# SCB_PLLs.net
KiCad netlist of a schematic drawn in Altium Designer
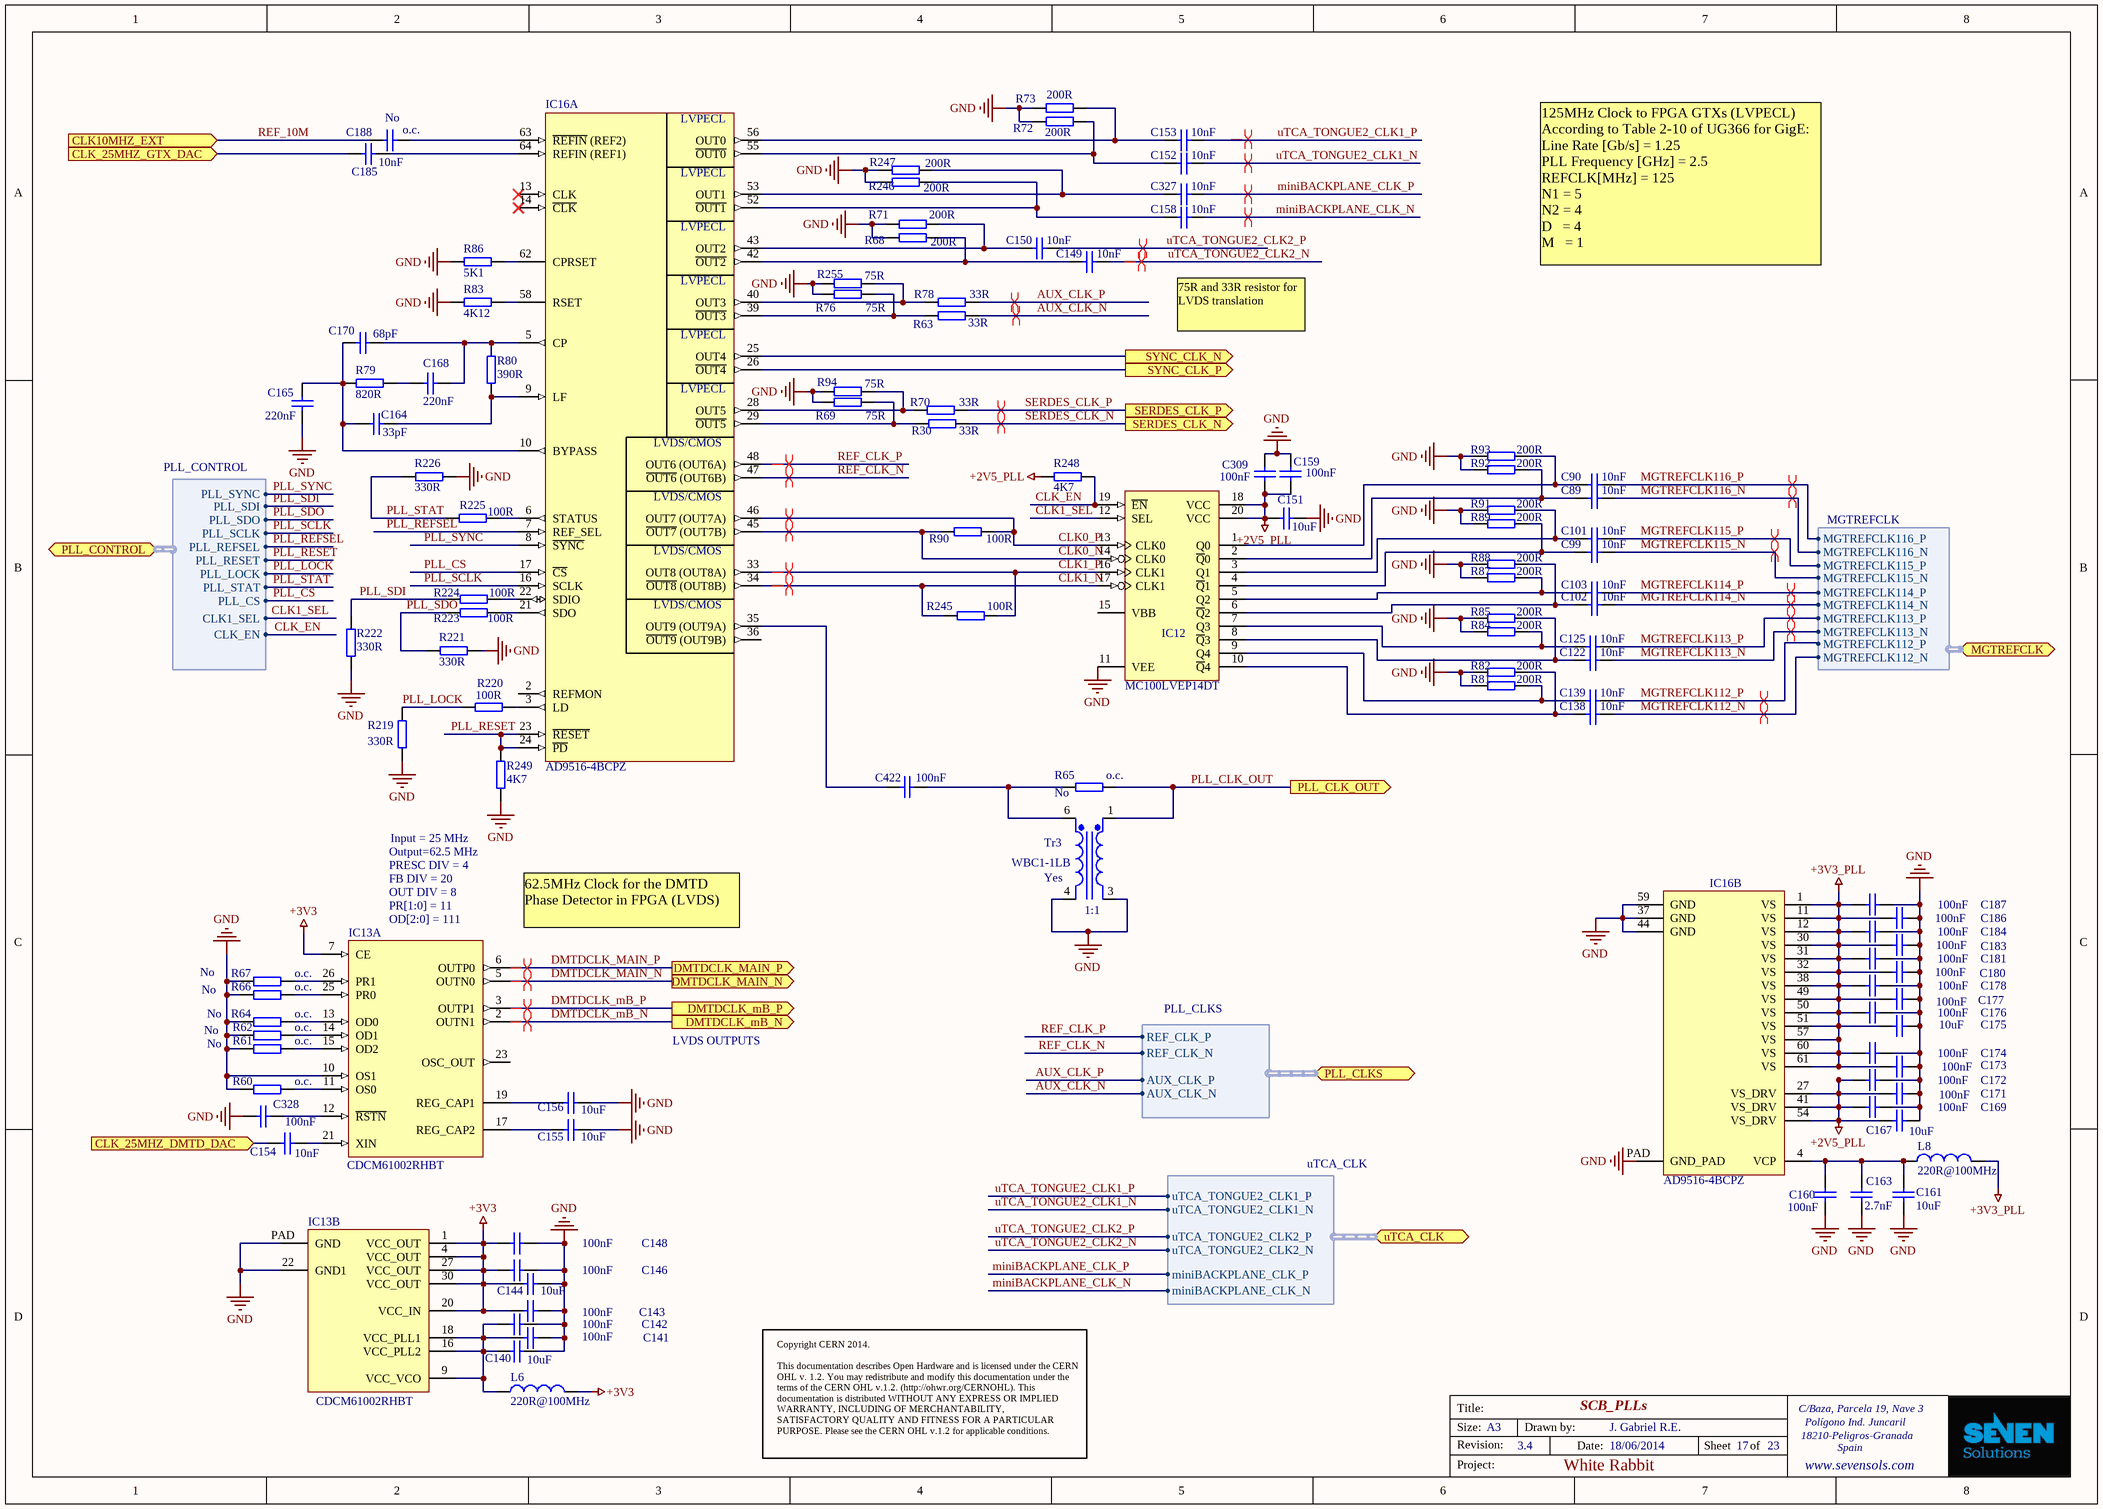
[diagram p0: SCB_PLLs.SchDoc]

(export (version "E")
  (design (tool "Eeschema 10.0.6"))
  (components
    (comp (ref "C89")
      (value "10nF")
      (footprint "CC1005-0402")
      (description "Capacitor")
      (fields (field (name "TOLERANCE") "±10%") (field (name "VOLTAGE") "25V"))
      (libsource (lib "wr_switch") (part "Cap"))
    )
    (comp (ref "C90")
      (value "10nF")
      (footprint "CC1005-0402")
      (description "Capacitor")
      (fields (field (name "TOLERANCE") "±10%") (field (name "VOLTAGE") "25V"))
      (libsource (lib "wr_switch") (part "Cap"))
    )
    (comp (ref "C99")
      (value "10nF")
      (footprint "CC1005-0402")
      (description "Capacitor")
      (fields (field (name "TOLERANCE") "±10%") (field (name "VOLTAGE") "25V"))
      (libsource (lib "wr_switch") (part "Cap"))
    )
    (comp (ref "C101")
      (value "10nF")
      (footprint "CC1005-0402")
      (description "Capacitor")
      (fields (field (name "TOLERANCE") "±10%") (field (name "VOLTAGE") "25V"))
      (libsource (lib "wr_switch") (part "Cap"))
    )
    (comp (ref "C102")
      (value "10nF")
      (footprint "CC1005-0402")
      (description "Capacitor")
      (fields (field (name "TOLERANCE") "±10%") (field (name "VOLTAGE") "25V"))
      (libsource (lib "wr_switch") (part "Cap"))
    )
    (comp (ref "C103")
      (value "10nF")
      (footprint "CC1005-0402")
      (description "Capacitor")
      (fields (field (name "TOLERANCE") "±10%") (field (name "VOLTAGE") "25V"))
      (libsource (lib "wr_switch") (part "Cap"))
    )
    (comp (ref "C122")
      (value "10nF")
      (footprint "CC1005-0402")
      (description "Capacitor")
      (fields (field (name "TOLERANCE") "±10%") (field (name "VOLTAGE") "25V"))
      (libsource (lib "wr_switch") (part "Cap"))
    )
    (comp (ref "C125")
      (value "10nF")
      (footprint "CC1005-0402")
      (description "Capacitor")
      (fields (field (name "TOLERANCE") "±10%") (field (name "VOLTAGE") "25V"))
      (libsource (lib "wr_switch") (part "Cap"))
    )
    (comp (ref "C138")
      (value "10nF")
      (footprint "CC1005-0402")
      (description "Capacitor")
      (fields (field (name "TOLERANCE") "±10%") (field (name "VOLTAGE") "25V"))
      (libsource (lib "wr_switch") (part "Cap"))
    )
    (comp (ref "C139")
      (value "10nF")
      (footprint "CC1005-0402")
      (description "Capacitor")
      (fields (field (name "TOLERANCE") "±10%") (field (name "VOLTAGE") "25V"))
      (libsource (lib "wr_switch") (part "Cap"))
    )
    (comp (ref "C140")
      (value "10uF")
      (footprint "CC1608-0603")
      (description "Capacitor")
      (fields (field (name "TOLERANCE") "±20%") (field (name "VOLTAGE") "6.3V"))
      (libsource (lib "wr_switch") (part "Cap"))
    )
    (comp (ref "C141")
      (value "100nF")
      (footprint "CC1005-0402")
      (description "Capacitor")
      (fields (field (name "TOLERANCE") "±10%") (field (name "VOLTAGE") "16V"))
      (libsource (lib "wr_switch") (part "Cap"))
    )
    (comp (ref "C142")
      (value "100nF")
      (footprint "CC1005-0402")
      (description "Capacitor")
      (fields (field (name "TOLERANCE") "±10%") (field (name "VOLTAGE") "16V"))
      (libsource (lib "wr_switch") (part "Cap"))
    )
    (comp (ref "C143")
      (value "100nF")
      (footprint "CC1005-0402")
      (description "Capacitor")
      (fields (field (name "TOLERANCE") "±10%") (field (name "VOLTAGE") "16V"))
      (libsource (lib "wr_switch") (part "Cap"))
    )
    (comp (ref "C144")
      (value "10uF")
      (footprint "CC1608-0603")
      (description "Capacitor")
      (fields (field (name "TOLERANCE") "±20%") (field (name "VOLTAGE") "6.3V"))
      (libsource (lib "wr_switch") (part "Cap"))
    )
    (comp (ref "C146")
      (value "100nF")
      (footprint "CC1005-0402")
      (description "Capacitor")
      (fields (field (name "TOLERANCE") "±10%") (field (name "VOLTAGE") "16V"))
      (libsource (lib "wr_switch") (part "Cap"))
    )
    (comp (ref "C148")
      (value "100nF")
      (footprint "CC1005-0402")
      (description "Capacitor")
      (fields (field (name "TOLERANCE") "±10%") (field (name "VOLTAGE") "16V"))
      (libsource (lib "wr_switch") (part "Cap"))
    )
    (comp (ref "C149")
      (value "10nF")
      (footprint "CC1005-0402")
      (description "Capacitor")
      (fields (field (name "TOLERANCE") "±10%") (field (name "VOLTAGE") "25V"))
      (libsource (lib "wr_switch") (part "Cap"))
    )
    (comp (ref "C150")
      (value "10nF")
      (footprint "CC1005-0402")
      (description "Capacitor")
      (fields (field (name "TOLERANCE") "±10%") (field (name "VOLTAGE") "25V"))
      (libsource (lib "wr_switch") (part "Cap"))
    )
    (comp (ref "C151")
      (value "10uF")
      (footprint "CC1608-0603")
      (description "Capacitor")
      (fields (field (name "TOLERANCE") "±20%") (field (name "VOLTAGE") "6.3V"))
      (libsource (lib "wr_switch") (part "Cap"))
    )
    (comp (ref "C152")
      (value "10nF")
      (footprint "CC1005-0402")
      (description "Capacitor")
      (fields (field (name "TOLERANCE") "±10%") (field (name "VOLTAGE") "25V"))
      (libsource (lib "wr_switch") (part "Cap"))
    )
    (comp (ref "C153")
      (value "10nF")
      (footprint "CC1005-0402")
      (description "Capacitor")
      (fields (field (name "TOLERANCE") "±10%") (field (name "VOLTAGE") "25V"))
      (libsource (lib "wr_switch") (part "Cap"))
    )
    (comp (ref "C154")
      (value "10nF")
      (footprint "CC1005-0402")
      (description "Capacitor")
      (fields (field (name "TOLERANCE") "±10%") (field (name "VOLTAGE") "25V"))
      (libsource (lib "wr_switch") (part "Cap"))
    )
    (comp (ref "C155")
      (value "10uF")
      (footprint "CC1608-0603")
      (description "Capacitor")
      (fields (field (name "TOLERANCE") "±20%") (field (name "VOLTAGE") "6.3V"))
      (libsource (lib "wr_switch") (part "Cap"))
    )
    (comp (ref "C156")
      (value "10uF")
      (footprint "CC1608-0603")
      (description "Capacitor")
      (fields (field (name "TOLERANCE") "±20%") (field (name "VOLTAGE") "6.3V"))
      (libsource (lib "wr_switch") (part "Cap"))
    )
    (comp (ref "C158")
      (value "10nF")
      (footprint "CC1005-0402")
      (description "Capacitor")
      (fields (field (name "TOLERANCE") "±10%") (field (name "VOLTAGE") "25V"))
      (libsource (lib "wr_switch") (part "Cap"))
    )
    (comp (ref "C159")
      (value "100nF")
      (footprint "CC1005-0402")
      (description "Capacitor")
      (fields (field (name "TOLERANCE") "±10%") (field (name "VOLTAGE") "16V"))
      (libsource (lib "wr_switch") (part "Cap"))
    )
    (comp (ref "C160")
      (value "100nF")
      (footprint "CC1005-0402")
      (description "Capacitor")
      (fields (field (name "TOLERANCE") "±10%") (field (name "VOLTAGE") "16V"))
      (libsource (lib "wr_switch") (part "Cap"))
    )
    (comp (ref "C161")
      (value "10uF")
      (footprint "CC1608-0603")
      (description "Capacitor")
      (fields (field (name "TOLERANCE") "±20%") (field (name "VOLTAGE") "6.3V"))
      (libsource (lib "wr_switch") (part "Cap"))
    )
    (comp (ref "C163")
      (value "2.7nF")
      (footprint "CC1005-0402")
      (description "Capacitor")
      (fields (field (name "TOLERANCE") "±10%") (field (name "VOLTAGE") "50V"))
      (libsource (lib "wr_switch") (part "Cap"))
    )
    (comp (ref "C164")
      (value "33pF")
      (footprint "CC1608-0603")
      (description "Capacitor")
      (fields (field (name "TOLERANCE") "±5%") (field (name "VOLTAGE") "50V"))
      (libsource (lib "wr_switch") (part "Cap"))
    )
    (comp (ref "C165")
      (value "220nF")
      (footprint "CC1608-0603")
      (description "Capacitor")
      (fields (field (name "TOLERANCE") "±10%") (field (name "VOLTAGE") "10V"))
      (libsource (lib "wr_switch") (part "Cap"))
    )
    (comp (ref "C167")
      (value "10uF")
      (footprint "CC1608-0603")
      (description "Capacitor")
      (fields (field (name "TOLERANCE") "±20%") (field (name "VOLTAGE") "6.3V"))
      (libsource (lib "wr_switch") (part "Cap"))
    )
    (comp (ref "C168")
      (value "220nF")
      (footprint "CC1608-0603")
      (description "Capacitor")
      (fields (field (name "TOLERANCE") "±10%") (field (name "VOLTAGE") "10V"))
      (libsource (lib "wr_switch") (part "Cap"))
    )
    (comp (ref "C169")
      (value "100nF")
      (footprint "CC1005-0402")
      (description "Capacitor")
      (fields (field (name "TOLERANCE") "±10%") (field (name "VOLTAGE") "16V"))
      (libsource (lib "wr_switch") (part "Cap"))
    )
    (comp (ref "C170")
      (value "68pF")
      (footprint "CC1608-0603")
      (description "Capacitor")
      (fields (field (name "TOLERANCE") "±5%") (field (name "VOLTAGE") "50V"))
      (libsource (lib "wr_switch") (part "Cap"))
    )
    (comp (ref "C171")
      (value "100nF")
      (footprint "CC1005-0402")
      (description "Capacitor")
      (fields (field (name "TOLERANCE") "±10%") (field (name "VOLTAGE") "16V"))
      (libsource (lib "wr_switch") (part "Cap"))
    )
    (comp (ref "C172")
      (value "100nF")
      (footprint "CC1005-0402")
      (description "Capacitor")
      (fields (field (name "TOLERANCE") "±10%") (field (name "VOLTAGE") "16V"))
      (libsource (lib "wr_switch") (part "Cap"))
    )
    (comp (ref "C173")
      (value "100nF")
      (footprint "CC1005-0402")
      (description "Capacitor")
      (fields (field (name "TOLERANCE") "±10%") (field (name "VOLTAGE") "16V"))
      (libsource (lib "wr_switch") (part "Cap"))
    )
    (comp (ref "C174")
      (value "100nF")
      (footprint "CC1005-0402")
      (description "Capacitor")
      (fields (field (name "TOLERANCE") "±10%") (field (name "VOLTAGE") "16V"))
      (libsource (lib "wr_switch") (part "Cap"))
    )
    (comp (ref "C175")
      (value "10uF")
      (footprint "CC1608-0603")
      (description "Capacitor")
      (fields (field (name "TOLERANCE") "±20%") (field (name "VOLTAGE") "6.3V"))
      (libsource (lib "wr_switch") (part "Cap"))
    )
    (comp (ref "C176")
      (value "100nF")
      (footprint "CC1005-0402")
      (description "Capacitor")
      (fields (field (name "TOLERANCE") "±10%") (field (name "VOLTAGE") "16V"))
      (libsource (lib "wr_switch") (part "Cap"))
    )
    (comp (ref "C177")
      (value "100nF")
      (footprint "CC1005-0402")
      (description "Capacitor")
      (fields (field (name "TOLERANCE") "±10%") (field (name "VOLTAGE") "16V"))
      (libsource (lib "wr_switch") (part "Cap"))
    )
    (comp (ref "C178")
      (value "100nF")
      (footprint "CC1005-0402")
      (description "Capacitor")
      (fields (field (name "TOLERANCE") "±10%") (field (name "VOLTAGE") "16V"))
      (libsource (lib "wr_switch") (part "Cap"))
    )
    (comp (ref "C180")
      (value "100nF")
      (footprint "CC1005-0402")
      (description "Capacitor")
      (fields (field (name "TOLERANCE") "±10%") (field (name "VOLTAGE") "16V"))
      (libsource (lib "wr_switch") (part "Cap"))
    )
    (comp (ref "C181")
      (value "100nF")
      (footprint "CC1005-0402")
      (description "Capacitor")
      (fields (field (name "TOLERANCE") "±10%") (field (name "VOLTAGE") "16V"))
      (libsource (lib "wr_switch") (part "Cap"))
    )
    (comp (ref "C183")
      (value "100nF")
      (footprint "CC1005-0402")
      (description "Capacitor")
      (fields (field (name "TOLERANCE") "±10%") (field (name "VOLTAGE") "16V"))
      (libsource (lib "wr_switch") (part "Cap"))
    )
    (comp (ref "C184")
      (value "100nF")
      (footprint "CC1005-0402")
      (description "Capacitor")
      (fields (field (name "TOLERANCE") "±10%") (field (name "VOLTAGE") "16V"))
      (libsource (lib "wr_switch") (part "Cap"))
    )
    (comp (ref "C185")
      (value "10nF")
      (footprint "CC1005-0402")
      (description "Capacitor")
      (fields (field (name "TOLERANCE") "±10%") (field (name "VOLTAGE") "25V"))
      (libsource (lib "wr_switch") (part "Cap"))
    )
    (comp (ref "C186")
      (value "100nF")
      (footprint "CC1005-0402")
      (description "Capacitor")
      (fields (field (name "TOLERANCE") "±10%") (field (name "VOLTAGE") "16V"))
      (libsource (lib "wr_switch") (part "Cap"))
    )
    (comp (ref "C187")
      (value "100nF")
      (footprint "CC1005-0402")
      (description "Capacitor")
      (fields (field (name "TOLERANCE") "±10%") (field (name "VOLTAGE") "16V"))
      (libsource (lib "wr_switch") (part "Cap"))
    )
    (comp (ref "C188")
      (value "o.c.")
      (footprint "CC1005-0402")
      (description "Capacitor")
      (fields (field (name "TOLERANCE") "±10%") (field (name "VOLTAGE") "25V") (field (name "MOUNTED") "No"))
      (libsource (lib "wr_switch") (part "Cap"))
    )
    (comp (ref "C309")
      (value "100nF")
      (footprint "CC1005-0402")
      (description "Capacitor")
      (fields (field (name "TOLERANCE") "±10%") (field (name "VOLTAGE") "16V"))
      (libsource (lib "wr_switch") (part "Cap"))
    )
    (comp (ref "C327")
      (value "10nF")
      (footprint "CC1005-0402")
      (description "Capacitor")
      (fields (field (name "TOLERANCE") "±10%") (field (name "VOLTAGE") "25V"))
      (libsource (lib "wr_switch") (part "Cap"))
    )
    (comp (ref "C328")
      (value "100nF")
      (footprint "CC1005-0402")
      (description "Capacitor")
      (fields (field (name "TOLERANCE") "±10%") (field (name "VOLTAGE") "16V"))
      (libsource (lib "wr_switch") (part "Cap"))
    )
    (comp (ref "C422")
      (value "100nF")
      (footprint "CC1005-0402")
      (description "Capacitor")
      (fields (field (name "TOLERANCE") "±10%") (field (name "VOLTAGE") "16V"))
      (libsource (lib "wr_switch") (part "Cap"))
    )
    (comp (ref "IC12")
      (value "MC100LVEP14DT")
      (footprint "948E-02_N")
      (description "Low-Voltage 1:5 Differential LVECL/LVPECL/LVEPECL/HSTL Clock Driver")
      (libsource (lib "ON Semi Peripheral Clock Generator") (part "MC100LVEP14DT"))
    )
    (comp (ref "IC13")
      (value "CDCM61002RHBT")
      (footprint "QFN32_POWERPAD")
      (description "Low Jitter Clock Generator, Two Outpust, Integrated VCO")
      (fields (field (name "MANUFACTURER") "Texas Instruments"))
      (libsource (lib "wr_switch") (part "CDCM61002"))
    )
    (comp (ref "IC16")
      (value "AD9516-4BCPZ")
      (footprint "QFN50P900X900X100-64M")
      (description "PLL with clock fanout")
      (libsource (lib "wr_switch") (part "AD9516"))
    )
    (comp (ref "L6")
      (value "220R@100MHz Ferrite Bead")
      (footprint "0603")
      (description "ferrite bead")
      (fields (field (name "IMPEDANCE") "220R@100MHz"))
      (libsource (lib "wr_switch") (part "L_FERRITE_BEAD"))
    )
    (comp (ref "L8")
      (value "220R@100MHz Ferrite Bead")
      (footprint "0603")
      (description "ferrite bead")
      (fields (field (name "IMPEDANCE") "220R@100MHz"))
      (libsource (lib "wr_switch") (part "L_FERRITE_BEAD"))
    )
    (comp (ref "R30")
      (value "33R")
      (footprint "0402")
      (description "SMD Resistor")
      (fields (field (name "TOLERANCE") "±1%"))
      (libsource (lib "wr_switch") (part "RES_SMD"))
    )
    (comp (ref "R60")
      (value "o.c.")
      (footprint "0402")
      (description "SMD Resistor")
      (libsource (lib "wr_switch") (part "RES_SMD"))
    )
    (comp (ref "R61")
      (value "o.c.")
      (footprint "0402")
      (description "SMD Resistor")
      (fields (field (name "MOUNTED") "No"))
      (libsource (lib "wr_switch") (part "RES_SMD"))
    )
    (comp (ref "R62")
      (value "o.c.")
      (footprint "0402")
      (description "SMD Resistor")
      (fields (field (name "MOUNTED") "No"))
      (libsource (lib "wr_switch") (part "RES_SMD"))
    )
    (comp (ref "R63")
      (value "33R")
      (footprint "0402")
      (description "SMD Resistor")
      (fields (field (name "TOLERANCE") "±1%"))
      (libsource (lib "wr_switch") (part "RES_SMD"))
    )
    (comp (ref "R64")
      (value "o.c.")
      (footprint "0402")
      (description "SMD Resistor")
      (fields (field (name "MOUNTED") "No"))
      (libsource (lib "wr_switch") (part "RES_SMD"))
    )
    (comp (ref "R65")
      (value "o.c.")
      (footprint "0402")
      (description "SMD Resistor")
      (fields (field (name "MOUNTED") "No"))
      (libsource (lib "wr_switch") (part "RES_SMD"))
    )
    (comp (ref "R66")
      (value "o.c.")
      (footprint "0402")
      (description "SMD Resistor")
      (fields (field (name "MOUNTED") "No"))
      (libsource (lib "wr_switch") (part "RES_SMD"))
    )
    (comp (ref "R67")
      (value "o.c.")
      (footprint "0402")
      (description "SMD Resistor")
      (fields (field (name "MOUNTED") "No"))
      (libsource (lib "wr_switch") (part "RES_SMD"))
    )
    (comp (ref "R68")
      (value "200R")
      (footprint "0402")
      (description "SMD Resistor")
      (fields (field (name "TOLERANCE") "±1%"))
      (libsource (lib "wr_switch") (part "RES_SMD"))
    )
    (comp (ref "R69")
      (value "75R")
      (footprint "0402")
      (description "SMD Resistor")
      (fields (field (name "TOLERANCE") "±1%"))
      (libsource (lib "wr_switch") (part "RES_SMD"))
    )
    (comp (ref "R70")
      (value "33R")
      (footprint "0402")
      (description "SMD Resistor")
      (fields (field (name "TOLERANCE") "±1%"))
      (libsource (lib "wr_switch") (part "RES_SMD"))
    )
    (comp (ref "R71")
      (value "200R")
      (footprint "0402")
      (description "SMD Resistor")
      (fields (field (name "TOLERANCE") "±1%"))
      (libsource (lib "wr_switch") (part "RES_SMD"))
    )
    (comp (ref "R72")
      (value "200R")
      (footprint "0402")
      (description "SMD Resistor")
      (fields (field (name "TOLERANCE") "±1%"))
      (libsource (lib "wr_switch") (part "RES_SMD"))
    )
    (comp (ref "R73")
      (value "200R")
      (footprint "0402")
      (description "SMD Resistor")
      (fields (field (name "TOLERANCE") "±1%"))
      (libsource (lib "wr_switch") (part "RES_SMD"))
    )
    (comp (ref "R76")
      (value "75R")
      (footprint "0402")
      (description "SMD Resistor")
      (fields (field (name "TOLERANCE") "±1%"))
      (libsource (lib "wr_switch") (part "RES_SMD"))
    )
    (comp (ref "R78")
      (value "33R")
      (footprint "0402")
      (description "SMD Resistor")
      (fields (field (name "TOLERANCE") "±1%"))
      (libsource (lib "wr_switch") (part "RES_SMD"))
    )
    (comp (ref "R79")
      (value "820R")
      (footprint "0603")
      (description "SMD Resistor")
      (fields (field (name "TOLERANCE") "±1%"))
      (libsource (lib "wr_switch") (part "RES_SMD"))
    )
    (comp (ref "R80")
      (value "390R")
      (footprint "0603")
      (description "SMD Resistor")
      (fields (field (name "TOLERANCE") "±1%"))
      (libsource (lib "wr_switch") (part "RES_SMD"))
    )
    (comp (ref "R81")
      (value "200R")
      (footprint "0402")
      (description "SMD Resistor")
      (fields (field (name "TOLERANCE") "±1%"))
      (libsource (lib "wr_switch") (part "RES_SMD"))
    )
    (comp (ref "R82")
      (value "200R")
      (footprint "0402")
      (description "SMD Resistor")
      (fields (field (name "TOLERANCE") "±1%"))
      (libsource (lib "wr_switch") (part "RES_SMD"))
    )
    (comp (ref "R83")
      (value "4K12")
      (footprint "0402")
      (description "SMD Resistor")
      (fields (field (name "TOLERANCE") "±1%"))
      (libsource (lib "wr_switch") (part "RES_SMD"))
    )
    (comp (ref "R84")
      (value "200R")
      (footprint "0402")
      (description "SMD Resistor")
      (fields (field (name "TOLERANCE") "±1%"))
      (libsource (lib "wr_switch") (part "RES_SMD"))
    )
    (comp (ref "R85")
      (value "200R")
      (footprint "0402")
      (description "SMD Resistor")
      (fields (field (name "TOLERANCE") "±1%"))
      (libsource (lib "wr_switch") (part "RES_SMD"))
    )
    (comp (ref "R86")
      (value "5K1")
      (footprint "0402")
      (description "SMD Resistor")
      (fields (field (name "TOLERANCE") "±1%"))
      (libsource (lib "wr_switch") (part "RES_SMD"))
    )
    (comp (ref "R87")
      (value "200R")
      (footprint "0402")
      (description "SMD Resistor")
      (fields (field (name "TOLERANCE") "±1%"))
      (libsource (lib "wr_switch") (part "RES_SMD"))
    )
    (comp (ref "R88")
      (value "200R")
      (footprint "0402")
      (description "SMD Resistor")
      (fields (field (name "TOLERANCE") "±1%"))
      (libsource (lib "wr_switch") (part "RES_SMD"))
    )
    (comp (ref "R89")
      (value "200R")
      (footprint "0402")
      (description "SMD Resistor")
      (fields (field (name "TOLERANCE") "±1%"))
      (libsource (lib "wr_switch") (part "RES_SMD"))
    )
    (comp (ref "R90")
      (value "100R")
      (footprint "0402")
      (description "SMD Resistor")
      (fields (field (name "TOLERANCE") "±1%"))
      (libsource (lib "wr_switch") (part "RES_SMD"))
    )
    (comp (ref "R91")
      (value "200R")
      (footprint "0402")
      (description "SMD Resistor")
      (fields (field (name "TOLERANCE") "±1%"))
      (libsource (lib "wr_switch") (part "RES_SMD"))
    )
    (comp (ref "R92")
      (value "200R")
      (footprint "0402")
      (description "SMD Resistor")
      (fields (field (name "TOLERANCE") "±1%"))
      (libsource (lib "wr_switch") (part "RES_SMD"))
    )
    (comp (ref "R93")
      (value "200R")
      (footprint "0402")
      (description "SMD Resistor")
      (fields (field (name "TOLERANCE") "±1%"))
      (libsource (lib "wr_switch") (part "RES_SMD"))
    )
    (comp (ref "R94")
      (value "75R")
      (footprint "0402")
      (description "SMD Resistor")
      (fields (field (name "TOLERANCE") "±1%"))
      (libsource (lib "wr_switch") (part "RES_SMD"))
    )
    (comp (ref "R219")
      (value "330R")
      (footprint "0402")
      (description "SMD Resistor")
      (fields (field (name "TOLERANCE") "±1%"))
      (libsource (lib "wr_switch") (part "RES_SMD"))
    )
    (comp (ref "R220")
      (value "100R")
      (footprint "0402")
      (description "SMD Resistor")
      (fields (field (name "TOLERANCE") "±1%"))
      (libsource (lib "wr_switch") (part "RES_SMD"))
    )
    (comp (ref "R221")
      (value "330R")
      (footprint "0402")
      (description "SMD Resistor")
      (fields (field (name "TOLERANCE") "±1%"))
      (libsource (lib "wr_switch") (part "RES_SMD"))
    )
    (comp (ref "R222")
      (value "330R")
      (footprint "0402")
      (description "SMD Resistor")
      (fields (field (name "TOLERANCE") "±1%"))
      (libsource (lib "wr_switch") (part "RES_SMD"))
    )
    (comp (ref "R223")
      (value "100R")
      (footprint "0402")
      (description "SMD Resistor")
      (fields (field (name "TOLERANCE") "±1%"))
      (libsource (lib "wr_switch") (part "RES_SMD"))
    )
    (comp (ref "R224")
      (value "100R")
      (footprint "0402")
      (description "SMD Resistor")
      (fields (field (name "TOLERANCE") "±1%"))
      (libsource (lib "wr_switch") (part "RES_SMD"))
    )
    (comp (ref "R225")
      (value "100R")
      (footprint "0402")
      (description "SMD Resistor")
      (fields (field (name "TOLERANCE") "±1%"))
      (libsource (lib "wr_switch") (part "RES_SMD"))
    )
    (comp (ref "R226")
      (value "330R")
      (footprint "0402")
      (description "SMD Resistor")
      (fields (field (name "TOLERANCE") "±1%"))
      (libsource (lib "wr_switch") (part "RES_SMD"))
    )
    (comp (ref "R245")
      (value "100R")
      (footprint "0402")
      (description "SMD Resistor")
      (fields (field (name "TOLERANCE") "±1%"))
      (libsource (lib "wr_switch") (part "RES_SMD"))
    )
    (comp (ref "R246")
      (value "200R")
      (footprint "0402")
      (description "SMD Resistor")
      (fields (field (name "TOLERANCE") "±1%"))
      (libsource (lib "wr_switch") (part "RES_SMD"))
    )
    (comp (ref "R247")
      (value "200R")
      (footprint "0402")
      (description "SMD Resistor")
      (fields (field (name "TOLERANCE") "±1%"))
      (libsource (lib "wr_switch") (part "RES_SMD"))
    )
    (comp (ref "R248")
      (value "4K7")
      (footprint "0402")
      (description "SMD Resistor")
      (fields (field (name "TOLERANCE") "±1%"))
      (libsource (lib "wr_switch") (part "RES_SMD"))
    )
    (comp (ref "R249")
      (value "4K7")
      (footprint "0402")
      (description "SMD Resistor")
      (fields (field (name "TOLERANCE") "±1%"))
      (libsource (lib "wr_switch") (part "RES_SMD"))
    )
    (comp (ref "R255")
      (value "75R")
      (footprint "0402")
      (description "SMD Resistor")
      (fields (field (name "TOLERANCE") "±1%"))
      (libsource (lib "wr_switch") (part "RES_SMD"))
    )
    (comp (ref "Tr3")
      (value "WBC1-1LB")
      (footprint "SMT6P150P")
      (description "SMT Mini WideBand Transformer 1:1, 10uH,")
      (fields
        (field (name "MANUFACTURER") "Coilcraft")
        (field (name "ALTIUM_VALUE") "1:1")
        (field (name "MOUNTED") "Yes")
      )
      (libsource (lib "wr_switch") (part "WBC1-1LB"))
    )
  )
  (nets
    (net (code "5") (name "+2V5_PLL") (class "Default")
      (node (ref "C151") (pin "2") (pinfunction "2_2") (pintype "passive"))
      (node (ref "C159") (pin "2") (pinfunction "2_2") (pintype "passive"))
      (node (ref "C167") (pin "1") (pinfunction "1_1") (pintype "passive"))
      (node (ref "C169") (pin "2") (pinfunction "2_2") (pintype "passive"))
      (node (ref "C171") (pin "2") (pinfunction "2_2") (pintype "passive"))
      (node (ref "C172") (pin "2") (pinfunction "2_2") (pintype "passive"))
      (node (ref "C309") (pin "2") (pinfunction "2_2") (pintype "passive"))
      (node (ref "IC12") (pin "18") (pinfunction "VCC_18") (pintype "power_in"))
      (node (ref "IC12") (pin "20") (pinfunction "VCC_20") (pintype "power_in"))
      (node (ref "IC16") (pin "27") (pinfunction "VS_DRV_27") (pintype "power_in"))
      (node (ref "IC16") (pin "41") (pinfunction "VS_DRV_41") (pintype "power_in"))
      (node (ref "IC16") (pin "54") (pinfunction "VS_DRV_54") (pintype "power_in"))
      (node (ref "R248") (pin "2") (pinfunction "2_2") (pintype "passive"))
    )
    (net (code "6") (name "+3V3") (class "Default")
      (node (ref "C143") (pin "2") (pinfunction "2_2") (pintype "passive"))
      (node (ref "C144") (pin "1") (pinfunction "1_1") (pintype "passive"))
      (node (ref "C146") (pin "2") (pinfunction "2_2") (pintype "passive"))
      (node (ref "C148") (pin "2") (pinfunction "2_2") (pintype "passive"))
      (node (ref "IC13") (pin "1") (pinfunction "VCC_OUT_1") (pintype "power_in"))
      (node (ref "IC13") (pin "20") (pinfunction "VCC_IN_20") (pintype "power_in"))
      (node (ref "IC13") (pin "27") (pinfunction "VCC_OUT_27") (pintype "power_in"))
      (node (ref "IC13") (pin "30") (pinfunction "VCC_OUT_30") (pintype "power_in"))
      (node (ref "IC13") (pin "4") (pinfunction "VCC_OUT_4") (pintype "power_in"))
      (node (ref "IC13") (pin "7") (pinfunction "CE_7") (pintype "input"))
      (node (ref "L6") (pin "2") (pinfunction "2_2") (pintype "passive"))
    )
    (net (code "7") (name "+3V3_PLL") (class "Default")
      (node (ref "C173") (pin "2") (pinfunction "2_2") (pintype "passive"))
      (node (ref "C174") (pin "2") (pinfunction "2_2") (pintype "passive"))
      (node (ref "C175") (pin "1") (pinfunction "1_1") (pintype "passive"))
      (node (ref "C176") (pin "2") (pinfunction "2_2") (pintype "passive"))
      (node (ref "C177") (pin "2") (pinfunction "2_2") (pintype "passive"))
      (node (ref "C178") (pin "2") (pinfunction "2_2") (pintype "passive"))
      (node (ref "C180") (pin "2") (pinfunction "2_2") (pintype "passive"))
      (node (ref "C181") (pin "2") (pinfunction "2_2") (pintype "passive"))
      (node (ref "C183") (pin "2") (pinfunction "2_2") (pintype "passive"))
      (node (ref "C184") (pin "2") (pinfunction "2_2") (pintype "passive"))
      (node (ref "C186") (pin "2") (pinfunction "2_2") (pintype "passive"))
      (node (ref "C187") (pin "2") (pinfunction "2_2") (pintype "passive"))
      (node (ref "IC16") (pin "1") (pinfunction "VS_1") (pintype "power_in"))
      (node (ref "IC16") (pin "11") (pinfunction "VS_11") (pintype "power_in"))
      (node (ref "IC16") (pin "12") (pinfunction "VS_12") (pintype "power_in"))
      (node (ref "IC16") (pin "30") (pinfunction "VS_30") (pintype "power_in"))
      (node (ref "IC16") (pin "31") (pinfunction "VS_31") (pintype "power_in"))
      (node (ref "IC16") (pin "32") (pinfunction "VS_32") (pintype "power_in"))
      (node (ref "IC16") (pin "38") (pinfunction "VS_38") (pintype "power_in"))
      (node (ref "IC16") (pin "49") (pinfunction "VS_49") (pintype "power_in"))
      (node (ref "IC16") (pin "50") (pinfunction "VS_50") (pintype "power_in"))
      (node (ref "IC16") (pin "51") (pinfunction "VS_51") (pintype "power_in"))
      (node (ref "IC16") (pin "57") (pinfunction "VS_57") (pintype "power_in"))
      (node (ref "IC16") (pin "60") (pinfunction "VS_60") (pintype "power_in"))
      (node (ref "IC16") (pin "61") (pinfunction "VS_61") (pintype "power_in"))
      (node (ref "L8") (pin "2") (pinfunction "2_2") (pintype "passive"))
    )
    (net (code "8") (name "/AUX_CLK_N") (class "Default")
      (node (ref "R63") (pin "2") (pinfunction "2_2") (pintype "passive"))
    )
    (net (code "9") (name "/AUX_CLK_P") (class "Default")
      (node (ref "R78") (pin "2") (pinfunction "2_2") (pintype "passive"))
    )
    (net (code "10") (name "/CLK0_N") (class "Default")
      (node (ref "IC12") (pin "14") (pinfunction "CLK0_14") (pintype "input"))
      (node (ref "IC16") (pin "45") (pinfunction "~{OUT7}_(OUT7B)_45") (pintype "output"))
      (node (ref "R90") (pin "1") (pinfunction "1_1") (pintype "passive"))
    )
    (net (code "11") (name "/CLK0_P") (class "Default")
      (node (ref "IC12") (pin "13") (pinfunction "CLK0_13") (pintype "input"))
      (node (ref "IC16") (pin "46") (pinfunction "OUT7_(OUT7A)_46") (pintype "output"))
      (node (ref "R90") (pin "2") (pinfunction "2_2") (pintype "passive"))
    )
    (net (code "12") (name "/CLK1_N") (class "Default")
      (node (ref "IC12") (pin "17") (pinfunction "CLK1_17") (pintype "input"))
      (node (ref "IC16") (pin "34") (pinfunction "~{OUT8}_(OUT8B)_34") (pintype "output"))
      (node (ref "R245") (pin "1") (pinfunction "1_1") (pintype "passive"))
    )
    (net (code "13") (name "/CLK1_P") (class "Default")
      (node (ref "IC12") (pin "16") (pinfunction "CLK1_16") (pintype "input"))
      (node (ref "IC16") (pin "33") (pinfunction "OUT8_(OUT8A)_33") (pintype "output"))
      (node (ref "R245") (pin "2") (pinfunction "2_2") (pintype "passive"))
    )
    (net (code "14") (name "/CLK1_SEL") (class "Default")
      (node (ref "IC12") (pin "12") (pinfunction "SEL_12") (pintype "input"))
    )
    (net (code "15") (name "/CLK_25MHZ_DMTD_DAC") (class "Default")
      (node (ref "C154") (pin "2") (pinfunction "2_2") (pintype "passive"))
    )
    (net (code "16") (name "/CLK_25MHZ_GTX_DAC") (class "Default")
      (node (ref "C185") (pin "1") (pinfunction "1_1") (pintype "passive"))
    )
    (net (code "17") (name "/CLK_EN") (class "Default")
      (node (ref "IC12") (pin "19") (pinfunction "~{EN}_19") (pintype "input"))
      (node (ref "R248") (pin "1") (pinfunction "1_1") (pintype "passive"))
    )
    (net (code "18") (name "/DMTDCLK_MAIN_N") (class "Default")
      (node (ref "IC13") (pin "5") (pinfunction "OUTN0_5") (pintype "output"))
    )
    (net (code "19") (name "/DMTDCLK_MAIN_P") (class "Default")
      (node (ref "IC13") (pin "6") (pinfunction "OUTP0_6") (pintype "output"))
    )
    (net (code "20") (name "/DMTDCLK_mB_N") (class "Default")
      (node (ref "IC13") (pin "2") (pinfunction "OUTN1_2") (pintype "output"))
    )
    (net (code "21") (name "/DMTDCLK_mB_P") (class "Default")
      (node (ref "IC13") (pin "3") (pinfunction "OUTP1_3") (pintype "output"))
    )
    (net (code "22") (name "/MGTREFCLK112_N") (class "Default")
      (node (ref "C138") (pin "1") (pinfunction "1_1") (pintype "passive"))
    )
    (net (code "23") (name "/MGTREFCLK112_P") (class "Default")
      (node (ref "C139") (pin "1") (pinfunction "1_1") (pintype "passive"))
    )
    (net (code "24") (name "/MGTREFCLK113_N") (class "Default")
      (node (ref "C122") (pin "1") (pinfunction "1_1") (pintype "passive"))
    )
    (net (code "25") (name "/MGTREFCLK113_P") (class "Default")
      (node (ref "C125") (pin "1") (pinfunction "1_1") (pintype "passive"))
    )
    (net (code "26") (name "/MGTREFCLK114_N") (class "Default")
      (node (ref "C102") (pin "1") (pinfunction "1_1") (pintype "passive"))
    )
    (net (code "27") (name "/MGTREFCLK114_P") (class "Default")
      (node (ref "C103") (pin "1") (pinfunction "1_1") (pintype "passive"))
    )
    (net (code "28") (name "/MGTREFCLK115_N") (class "Default")
      (node (ref "C99") (pin "1") (pinfunction "1_1") (pintype "passive"))
    )
    (net (code "29") (name "/MGTREFCLK115_P") (class "Default")
      (node (ref "C101") (pin "1") (pinfunction "1_1") (pintype "passive"))
    )
    (net (code "30") (name "/MGTREFCLK116_N") (class "Default")
      (node (ref "C89") (pin "1") (pinfunction "1_1") (pintype "passive"))
    )
    (net (code "31") (name "/MGTREFCLK116_P") (class "Default")
      (node (ref "C90") (pin "1") (pinfunction "1_1") (pintype "passive"))
    )
    (net (code "32") (name "/PLL_CLK_OUT") (class "Default")
      (node (ref "R65") (pin "1") (pinfunction "1_1") (pintype "passive"))
      (node (ref "Tr3") (pin "1") (pinfunction "Sec+_1") (pintype "passive"))
    )
    (net (code "33") (name "/PLL_CS") (class "Default")
      (node (ref "IC16") (pin "17") (pinfunction "~{CS}_17") (pintype "input"))
    )
    (net (code "34") (name "/PLL_LOCK") (class "Default")
      (node (ref "R219") (pin "2") (pinfunction "2_2") (pintype "passive"))
      (node (ref "R220") (pin "2") (pinfunction "2_2") (pintype "passive"))
    )
    (net (code "35") (name "/PLL_REFSEL") (class "Default")
      (node (ref "IC16") (pin "7") (pinfunction "REF_SEL_7") (pintype "input"))
    )
    (net (code "36") (name "/PLL_RESET") (class "Default")
      (node (ref "IC16") (pin "23") (pinfunction "~{RESET}_23") (pintype "input"))
      (node (ref "IC16") (pin "24") (pinfunction "~{PD}_24") (pintype "input"))
      (node (ref "R249") (pin "2") (pinfunction "2_2") (pintype "passive"))
    )
    (net (code "37") (name "/PLL_SCLK") (class "Default")
      (node (ref "IC16") (pin "16") (pinfunction "SCLK_16") (pintype "input"))
    )
    (net (code "38") (name "/PLL_SDI") (class "Default")
      (node (ref "R222") (pin "2") (pinfunction "2_2") (pintype "passive"))
      (node (ref "R224") (pin "2") (pinfunction "2_2") (pintype "passive"))
    )
    (net (code "39") (name "/PLL_SDO") (class "Default")
      (node (ref "R221") (pin "2") (pinfunction "2_2") (pintype "passive"))
      (node (ref "R223") (pin "2") (pinfunction "2_2") (pintype "passive"))
    )
    (net (code "40") (name "/PLL_STAT") (class "Default")
      (node (ref "R225") (pin "2") (pinfunction "2_2") (pintype "passive"))
      (node (ref "R226") (pin "2") (pinfunction "2_2") (pintype "passive"))
    )
    (net (code "41") (name "/PLL_SYNC") (class "Default")
      (node (ref "IC16") (pin "8") (pinfunction "~{SYNC}_8") (pintype "input"))
    )
    (net (code "42") (name "/REF_10M") (class "Default")
      (node (ref "C188") (pin "1") (pinfunction "1_1") (pintype "passive"))
    )
    (net (code "43") (name "/REF_CLK_N") (class "Default")
      (node (ref "IC16") (pin "47") (pinfunction "~{OUT6}_(OUT6B)_47") (pintype "output"))
    )
    (net (code "44") (name "/REF_CLK_P") (class "Default")
      (node (ref "IC16") (pin "48") (pinfunction "OUT6_(OUT6A)_48") (pintype "output"))
    )
    (net (code "45") (name "/SERDES_CLK_N") (class "Default")
      (node (ref "R30") (pin "2") (pinfunction "2_2") (pintype "passive"))
    )
    (net (code "46") (name "/SERDES_CLK_P") (class "Default")
      (node (ref "R70") (pin "2") (pinfunction "2_2") (pintype "passive"))
    )
    (net (code "47") (name "/SYNC_CLK_N") (class "Default")
      (node (ref "IC16") (pin "25") (pinfunction "OUT4_25") (pintype "output"))
    )
    (net (code "48") (name "/SYNC_CLK_P") (class "Default")
      (node (ref "IC16") (pin "26") (pinfunction "~{OUT4}_26") (pintype "output"))
    )
    (net (code "49") (name "/miniBACKPLANE_CLK_N") (class "Default")
      (node (ref "C158") (pin "1") (pinfunction "1_1") (pintype "passive"))
    )
    (net (code "50") (name "/miniBACKPLANE_CLK_P") (class "Default")
      (node (ref "C327") (pin "1") (pinfunction "1_1") (pintype "passive"))
    )
    (net (code "51") (name "/uTCA_TONGUE2_CLK1_N") (class "Default")
      (node (ref "C152") (pin "1") (pinfunction "1_1") (pintype "passive"))
    )
    (net (code "52") (name "/uTCA_TONGUE2_CLK1_P") (class "Default")
      (node (ref "C153") (pin "1") (pinfunction "1_1") (pintype "passive"))
    )
    (net (code "53") (name "/uTCA_TONGUE2_CLK2_N") (class "Default")
      (node (ref "C149") (pin "1") (pinfunction "1_1") (pintype "passive"))
    )
    (net (code "54") (name "/uTCA_TONGUE2_CLK2_P") (class "Default")
      (node (ref "C150") (pin "1") (pinfunction "1_1") (pintype "passive"))
    )
    (net (code "59") (name "GND") (class "Default")
      (node (ref "C140") (pin "2") (pinfunction "2_2") (pintype "passive"))
      (node (ref "C141") (pin "1") (pinfunction "1_1") (pintype "passive"))
      (node (ref "C142") (pin "1") (pinfunction "1_1") (pintype "passive"))
      (node (ref "C143") (pin "1") (pinfunction "1_1") (pintype "passive"))
      (node (ref "C144") (pin "2") (pinfunction "2_2") (pintype "passive"))
      (node (ref "C146") (pin "1") (pinfunction "1_1") (pintype "passive"))
      (node (ref "C148") (pin "1") (pinfunction "1_1") (pintype "passive"))
      (node (ref "C151") (pin "1") (pinfunction "1_1") (pintype "passive"))
      (node (ref "C155") (pin "2") (pinfunction "2_2") (pintype "passive"))
      (node (ref "C156") (pin "2") (pinfunction "2_2") (pintype "passive"))
      (node (ref "C159") (pin "1") (pinfunction "1_1") (pintype "passive"))
      (node (ref "C160") (pin "2") (pinfunction "2_2") (pintype "passive"))
      (node (ref "C161") (pin "1") (pinfunction "1_1") (pintype "passive"))
      (node (ref "C163") (pin "1") (pinfunction "1_1") (pintype "passive"))
      (node (ref "C165") (pin "1") (pinfunction "1_1") (pintype "passive"))
      (node (ref "C167") (pin "2") (pinfunction "2_2") (pintype "passive"))
      (node (ref "C169") (pin "1") (pinfunction "1_1") (pintype "passive"))
      (node (ref "C171") (pin "1") (pinfunction "1_1") (pintype "passive"))
      (node (ref "C172") (pin "1") (pinfunction "1_1") (pintype "passive"))
      (node (ref "C173") (pin "1") (pinfunction "1_1") (pintype "passive"))
      (node (ref "C174") (pin "1") (pinfunction "1_1") (pintype "passive"))
      (node (ref "C175") (pin "2") (pinfunction "2_2") (pintype "passive"))
      (node (ref "C176") (pin "1") (pinfunction "1_1") (pintype "passive"))
      (node (ref "C177") (pin "1") (pinfunction "1_1") (pintype "passive"))
      (node (ref "C178") (pin "1") (pinfunction "1_1") (pintype "passive"))
      (node (ref "C180") (pin "1") (pinfunction "1_1") (pintype "passive"))
      (node (ref "C181") (pin "1") (pinfunction "1_1") (pintype "passive"))
      (node (ref "C183") (pin "1") (pinfunction "1_1") (pintype "passive"))
      (node (ref "C184") (pin "1") (pinfunction "1_1") (pintype "passive"))
      (node (ref "C186") (pin "1") (pinfunction "1_1") (pintype "passive"))
      (node (ref "C187") (pin "1") (pinfunction "1_1") (pintype "passive"))
      (node (ref "C309") (pin "1") (pinfunction "1_1") (pintype "passive"))
      (node (ref "C328") (pin "2") (pinfunction "2_2") (pintype "passive"))
      (node (ref "IC12") (pin "11") (pinfunction "VEE_11") (pintype "power_in"))
      (node (ref "IC13") (pin "10") (pinfunction "OS1_10") (pintype "input"))
      (node (ref "IC13") (pin "22") (pinfunction "GND1_22") (pintype "power_in"))
      (node (ref "IC13") (pin "PAD") (pinfunction "GND_PAD") (pintype "power_in"))
      (node (ref "IC16") (pin "37") (pinfunction "GND_37") (pintype "power_in"))
      (node (ref "IC16") (pin "44") (pinfunction "GND_44") (pintype "power_in"))
      (node (ref "IC16") (pin "59") (pinfunction "GND_59") (pintype "power_in"))
      (node (ref "IC16") (pin "PAD") (pinfunction "GND_PAD_PAD") (pintype "power_in"))
      (node (ref "R219") (pin "1") (pinfunction "1_1") (pintype "passive"))
      (node (ref "R221") (pin "1") (pinfunction "1_1") (pintype "passive"))
      (node (ref "R222") (pin "1") (pinfunction "1_1") (pintype "passive"))
      (node (ref "R226") (pin "1") (pinfunction "1_1") (pintype "passive"))
      (node (ref "R246") (pin "2") (pinfunction "2_2") (pintype "passive"))
      (node (ref "R247") (pin "2") (pinfunction "2_2") (pintype "passive"))
      (node (ref "R249") (pin "1") (pinfunction "1_1") (pintype "passive"))
      (node (ref "R255") (pin "1") (pinfunction "1_1") (pintype "passive"))
      (node (ref "R60") (pin "2") (pinfunction "2_2") (pintype "passive"))
      (node (ref "R61") (pin "2") (pinfunction "2_2") (pintype "passive"))
      (node (ref "R62") (pin "2") (pinfunction "2_2") (pintype "passive"))
      (node (ref "R64") (pin "2") (pinfunction "2_2") (pintype "passive"))
      (node (ref "R66") (pin "2") (pinfunction "2_2") (pintype "passive"))
      (node (ref "R67") (pin "2") (pinfunction "2_2") (pintype "passive"))
      (node (ref "R68") (pin "2") (pinfunction "2_2") (pintype "passive"))
      (node (ref "R69") (pin "1") (pinfunction "1_1") (pintype "passive"))
      (node (ref "R71") (pin "2") (pinfunction "2_2") (pintype "passive"))
      (node (ref "R72") (pin "2") (pinfunction "2_2") (pintype "passive"))
      (node (ref "R73") (pin "2") (pinfunction "2_2") (pintype "passive"))
      (node (ref "R76") (pin "1") (pinfunction "1_1") (pintype "passive"))
      (node (ref "R81") (pin "2") (pinfunction "2_2") (pintype "passive"))
      (node (ref "R82") (pin "2") (pinfunction "2_2") (pintype "passive"))
      (node (ref "R83") (pin "1") (pinfunction "1_1") (pintype "passive"))
      (node (ref "R84") (pin "2") (pinfunction "2_2") (pintype "passive"))
      (node (ref "R85") (pin "2") (pinfunction "2_2") (pintype "passive"))
      (node (ref "R86") (pin "1") (pinfunction "1_1") (pintype "passive"))
      (node (ref "R87") (pin "2") (pinfunction "2_2") (pintype "passive"))
      (node (ref "R88") (pin "2") (pinfunction "2_2") (pintype "passive"))
      (node (ref "R89") (pin "2") (pinfunction "2_2") (pintype "passive"))
      (node (ref "R91") (pin "2") (pinfunction "2_2") (pintype "passive"))
      (node (ref "R92") (pin "2") (pinfunction "2_2") (pintype "passive"))
      (node (ref "R93") (pin "2") (pinfunction "2_2") (pintype "passive"))
      (node (ref "R94") (pin "1") (pinfunction "1_1") (pintype "passive"))
      (node (ref "Tr3") (pin "3") (pinfunction "Sec-_3") (pintype "passive"))
      (node (ref "Tr3") (pin "4") (pinfunction "Pri-_4") (pintype "passive"))
    )
    (net (code "60") (name "Net-(C168-Pad1)") (class "Default")
      (node (ref "C168") (pin "1") (pinfunction "1_1") (pintype "passive"))
      (node (ref "R79") (pin "2") (pinfunction "2_2") (pintype "passive"))
    )
    (net (code "61") (name "Net-(IC12-Q0)") (class "Default")
      (node (ref "C90") (pin "2") (pinfunction "2_2") (pintype "passive"))
      (node (ref "IC12") (pin "1") (pinfunction "Q0_1") (pintype "open_emitter"))
      (node (ref "R93") (pin "1") (pinfunction "1_1") (pintype "passive"))
    )
    (net (code "62") (name "Net-(IC12-Q1)") (class "Default")
      (node (ref "C101") (pin "2") (pinfunction "2_2") (pintype "passive"))
      (node (ref "IC12") (pin "3") (pinfunction "Q1_3") (pintype "open_emitter"))
      (node (ref "R91") (pin "1") (pinfunction "1_1") (pintype "passive"))
    )
    (net (code "63") (name "Net-(IC12-Q2)") (class "Default")
      (node (ref "C103") (pin "2") (pinfunction "2_2") (pintype "passive"))
      (node (ref "IC12") (pin "5") (pinfunction "Q2_5") (pintype "open_emitter"))
      (node (ref "R87") (pin "1") (pinfunction "1_1") (pintype "passive"))
    )
    (net (code "64") (name "Net-(IC12-Q3)") (class "Default")
      (node (ref "C125") (pin "2") (pinfunction "2_2") (pintype "passive"))
      (node (ref "IC12") (pin "7") (pinfunction "Q3_7") (pintype "open_emitter"))
      (node (ref "R84") (pin "1") (pinfunction "1_1") (pintype "passive"))
    )
    (net (code "65") (name "Net-(IC12-Q4)") (class "Default")
      (node (ref "C139") (pin "2") (pinfunction "2_2") (pintype "passive"))
      (node (ref "IC12") (pin "9") (pinfunction "Q4_9") (pintype "open_emitter"))
      (node (ref "R81") (pin "1") (pinfunction "1_1") (pintype "passive"))
    )
    (net (code "66") (name "Net-(IC12-~{Q}0)") (class "Default")
      (node (ref "C89") (pin "2") (pinfunction "2_2") (pintype "passive"))
      (node (ref "IC12") (pin "2") (pinfunction "~{Q}0_2") (pintype "open_emitter"))
      (node (ref "R92") (pin "1") (pinfunction "1_1") (pintype "passive"))
    )
    (net (code "67") (name "Net-(IC12-~{Q}1)") (class "Default")
      (node (ref "C99") (pin "2") (pinfunction "2_2") (pintype "passive"))
      (node (ref "IC12") (pin "4") (pinfunction "~{Q}1_4") (pintype "open_emitter"))
      (node (ref "R89") (pin "1") (pinfunction "1_1") (pintype "passive"))
    )
    (net (code "68") (name "Net-(IC12-~{Q}2)") (class "Default")
      (node (ref "C102") (pin "2") (pinfunction "2_2") (pintype "passive"))
      (node (ref "IC12") (pin "6") (pinfunction "~{Q}2_6") (pintype "open_emitter"))
      (node (ref "R88") (pin "1") (pinfunction "1_1") (pintype "passive"))
    )
    (net (code "69") (name "Net-(IC12-~{Q}3)") (class "Default")
      (node (ref "C122") (pin "2") (pinfunction "2_2") (pintype "passive"))
      (node (ref "IC12") (pin "8") (pinfunction "~{Q}3_8") (pintype "open_emitter"))
      (node (ref "R85") (pin "1") (pinfunction "1_1") (pintype "passive"))
    )
    (net (code "70") (name "Net-(IC12-~{Q}4)") (class "Default")
      (node (ref "C138") (pin "2") (pinfunction "2_2") (pintype "passive"))
      (node (ref "IC12") (pin "10") (pinfunction "~{Q}4_10") (pintype "open_emitter"))
      (node (ref "R82") (pin "1") (pinfunction "1_1") (pintype "passive"))
    )
    (net (code "71") (name "Net-(IC13A-OD0)") (class "Default")
      (node (ref "IC13") (pin "13") (pinfunction "OD0_13") (pintype "input"))
      (node (ref "R64") (pin "1") (pinfunction "1_1") (pintype "passive"))
    )
    (net (code "72") (name "Net-(IC13A-OD1)") (class "Default")
      (node (ref "IC13") (pin "14") (pinfunction "OD1_14") (pintype "input"))
      (node (ref "R62") (pin "1") (pinfunction "1_1") (pintype "passive"))
    )
    (net (code "73") (name "Net-(IC13A-OD2)") (class "Default")
      (node (ref "IC13") (pin "15") (pinfunction "OD2_15") (pintype "input"))
      (node (ref "R61") (pin "1") (pinfunction "1_1") (pintype "passive"))
    )
    (net (code "74") (name "Net-(IC13A-OS0)") (class "Default")
      (node (ref "IC13") (pin "11") (pinfunction "OS0_11") (pintype "input"))
      (node (ref "R60") (pin "1") (pinfunction "1_1") (pintype "passive"))
    )
    (net (code "75") (name "Net-(IC13A-PR0)") (class "Default")
      (node (ref "IC13") (pin "25") (pinfunction "PR0_25") (pintype "input"))
      (node (ref "R66") (pin "1") (pinfunction "1_1") (pintype "passive"))
    )
    (net (code "76") (name "Net-(IC13A-PR1)") (class "Default")
      (node (ref "IC13") (pin "26") (pinfunction "PR1_26") (pintype "input"))
      (node (ref "R67") (pin "1") (pinfunction "1_1") (pintype "passive"))
    )
    (net (code "77") (name "Net-(IC13A-REG_CAP1)") (class "Default")
      (node (ref "C156") (pin "1") (pinfunction "1_1") (pintype "passive"))
      (node (ref "IC13") (pin "19") (pinfunction "REG_CAP1_19") (pintype "passive"))
    )
    (net (code "78") (name "Net-(IC13A-REG_CAP2)") (class "Default")
      (node (ref "C155") (pin "1") (pinfunction "1_1") (pintype "passive"))
      (node (ref "IC13") (pin "17") (pinfunction "REG_CAP2_17") (pintype "passive"))
    )
    (net (code "79") (name "Net-(IC13A-XIN)") (class "Default")
      (node (ref "C154") (pin "1") (pinfunction "1_1") (pintype "passive"))
      (node (ref "IC13") (pin "21") (pinfunction "XIN_21") (pintype "input"))
    )
    (net (code "80") (name "Net-(IC13A-~{RSTN})") (class "Default")
      (node (ref "C328") (pin "1") (pinfunction "1_1") (pintype "passive"))
      (node (ref "IC13") (pin "12") (pinfunction "~{RSTN}_12") (pintype "input"))
    )
    (net (code "81") (name "Net-(IC13B-VCC_PLL1)") (class "Default")
      (node (ref "C140") (pin "1") (pinfunction "1_1") (pintype "passive"))
      (node (ref "C141") (pin "2") (pinfunction "2_2") (pintype "passive"))
      (node (ref "C142") (pin "2") (pinfunction "2_2") (pintype "passive"))
      (node (ref "IC13") (pin "16") (pinfunction "VCC_PLL2_16") (pintype "power_in"))
      (node (ref "IC13") (pin "18") (pinfunction "VCC_PLL1_18") (pintype "power_in"))
      (node (ref "IC13") (pin "9") (pinfunction "VCC_VCO_9") (pintype "power_in"))
      (node (ref "L6") (pin "1") (pinfunction "1_1") (pintype "passive"))
    )
    (net (code "82") (name "Net-(IC16A-BYPASS)") (class "Default")
      (node (ref "C164") (pin "1") (pinfunction "1_1") (pintype "passive"))
      (node (ref "C165") (pin "2") (pinfunction "2_2") (pintype "passive"))
      (node (ref "C170") (pin "1") (pinfunction "1_1") (pintype "passive"))
      (node (ref "IC16") (pin "10") (pinfunction "BYPASS_10") (pintype "output"))
      (node (ref "R79") (pin "1") (pinfunction "1_1") (pintype "passive"))
    )
    (net (code "83") (name "Net-(IC16A-CP)") (class "Default")
      (node (ref "C168") (pin "2") (pinfunction "2_2") (pintype "passive"))
      (node (ref "C170") (pin "2") (pinfunction "2_2") (pintype "passive"))
      (node (ref "IC16") (pin "5") (pinfunction "CP_5") (pintype "output"))
      (node (ref "R80") (pin "2") (pinfunction "2_2") (pintype "passive"))
    )
    (net (code "84") (name "Net-(IC16A-CPRSET)") (class "Default")
      (node (ref "IC16") (pin "62") (pinfunction "CPRSET_62") (pintype "passive"))
      (node (ref "R86") (pin "2") (pinfunction "2_2") (pintype "passive"))
    )
    (net (code "85") (name "Net-(IC16A-LD)") (class "Default")
      (node (ref "IC16") (pin "3") (pinfunction "LD_3") (pintype "output"))
      (node (ref "R220") (pin "1") (pinfunction "1_1") (pintype "passive"))
    )
    (net (code "86") (name "Net-(IC16A-LF)") (class "Default")
      (node (ref "C164") (pin "2") (pinfunction "2_2") (pintype "passive"))
      (node (ref "IC16") (pin "9") (pinfunction "LF_9") (pintype "input"))
      (node (ref "R80") (pin "1") (pinfunction "1_1") (pintype "passive"))
    )
    (net (code "87") (name "Net-(IC16A-OUT0)") (class "Default")
      (node (ref "C153") (pin "2") (pinfunction "2_2") (pintype "passive"))
      (node (ref "IC16") (pin "56") (pinfunction "OUT0_56") (pintype "output"))
      (node (ref "R73") (pin "1") (pinfunction "1_1") (pintype "passive"))
    )
    (net (code "88") (name "Net-(IC16A-OUT1)") (class "Default")
      (node (ref "C327") (pin "2") (pinfunction "2_2") (pintype "passive"))
      (node (ref "IC16") (pin "53") (pinfunction "OUT1_53") (pintype "output"))
      (node (ref "R247") (pin "1") (pinfunction "1_1") (pintype "passive"))
    )
    (net (code "89") (name "Net-(IC16A-OUT2)") (class "Default")
      (node (ref "C150") (pin "2") (pinfunction "2_2") (pintype "passive"))
      (node (ref "IC16") (pin "43") (pinfunction "OUT2_43") (pintype "output"))
      (node (ref "R71") (pin "1") (pinfunction "1_1") (pintype "passive"))
    )
    (net (code "90") (name "Net-(IC16A-OUT3)") (class "Default")
      (node (ref "IC16") (pin "40") (pinfunction "OUT3_40") (pintype "output"))
      (node (ref "R255") (pin "2") (pinfunction "2_2") (pintype "passive"))
      (node (ref "R78") (pin "1") (pinfunction "1_1") (pintype "passive"))
    )
    (net (code "91") (name "Net-(IC16A-OUT5)") (class "Default")
      (node (ref "IC16") (pin "28") (pinfunction "OUT5_28") (pintype "output"))
      (node (ref "R70") (pin "1") (pinfunction "1_1") (pintype "passive"))
      (node (ref "R94") (pin "2") (pinfunction "2_2") (pintype "passive"))
    )
    (net (code "92") (name "Net-(IC16A-OUT9_(OUT9A))") (class "Default")
      (node (ref "C422") (pin "1") (pinfunction "1_1") (pintype "passive"))
      (node (ref "IC16") (pin "35") (pinfunction "OUT9_(OUT9A)_35") (pintype "output"))
    )
    (net (code "93") (name "Net-(IC16A-REFIN_(REF1))") (class "Default")
      (node (ref "C185") (pin "2") (pinfunction "2_2") (pintype "passive"))
      (node (ref "IC16") (pin "64") (pinfunction "REFIN_(REF1)_64") (pintype "input"))
    )
    (net (code "94") (name "Net-(IC16A-RSET)") (class "Default")
      (node (ref "IC16") (pin "58") (pinfunction "RSET_58") (pintype "passive"))
      (node (ref "R83") (pin "2") (pinfunction "2_2") (pintype "passive"))
    )
    (net (code "95") (name "Net-(IC16A-SDIO)") (class "Default")
      (node (ref "IC16") (pin "22") (pinfunction "SDIO_22") (pintype "bidirectional"))
      (node (ref "R224") (pin "1") (pinfunction "1_1") (pintype "passive"))
    )
    (net (code "96") (name "Net-(IC16A-SDO)") (class "Default")
      (node (ref "IC16") (pin "21") (pinfunction "SDO_21") (pintype "output"))
      (node (ref "R223") (pin "1") (pinfunction "1_1") (pintype "passive"))
    )
    (net (code "97") (name "Net-(IC16A-STATUS)") (class "Default")
      (node (ref "IC16") (pin "6") (pinfunction "STATUS_6") (pintype "output"))
      (node (ref "R225") (pin "1") (pinfunction "1_1") (pintype "passive"))
    )
    (net (code "98") (name "Net-(IC16A-~{OUT0})") (class "Default")
      (node (ref "C152") (pin "2") (pinfunction "2_2") (pintype "passive"))
      (node (ref "IC16") (pin "55") (pinfunction "~{OUT0}_55") (pintype "output"))
      (node (ref "R72") (pin "1") (pinfunction "1_1") (pintype "passive"))
    )
    (net (code "99") (name "Net-(IC16A-~{OUT1})") (class "Default")
      (node (ref "C158") (pin "2") (pinfunction "2_2") (pintype "passive"))
      (node (ref "IC16") (pin "52") (pinfunction "~{OUT1}_52") (pintype "output"))
      (node (ref "R246") (pin "1") (pinfunction "1_1") (pintype "passive"))
    )
    (net (code "100") (name "Net-(IC16A-~{OUT2})") (class "Default")
      (node (ref "C149") (pin "2") (pinfunction "2_2") (pintype "passive"))
      (node (ref "IC16") (pin "42") (pinfunction "~{OUT2}_42") (pintype "output"))
      (node (ref "R68") (pin "1") (pinfunction "1_1") (pintype "passive"))
    )
    (net (code "101") (name "Net-(IC16A-~{OUT3})") (class "Default")
      (node (ref "IC16") (pin "39") (pinfunction "~{OUT3}_39") (pintype "output"))
      (node (ref "R63") (pin "1") (pinfunction "1_1") (pintype "passive"))
      (node (ref "R76") (pin "2") (pinfunction "2_2") (pintype "passive"))
    )
    (net (code "102") (name "Net-(IC16A-~{OUT5})") (class "Default")
      (node (ref "IC16") (pin "29") (pinfunction "~{OUT5}_29") (pintype "output"))
      (node (ref "R30") (pin "1") (pinfunction "1_1") (pintype "passive"))
      (node (ref "R69") (pin "2") (pinfunction "2_2") (pintype "passive"))
    )
    (net (code "103") (name "Net-(IC16A-~{REFIN}_(REF2))") (class "Default")
      (node (ref "C188") (pin "2") (pinfunction "2_2") (pintype "passive"))
      (node (ref "IC16") (pin "63") (pinfunction "~{REFIN}_(REF2)_63") (pintype "input"))
    )
    (net (code "104") (name "Net-(IC16B-VCP)") (class "Default")
      (node (ref "C160") (pin "1") (pinfunction "1_1") (pintype "passive"))
      (node (ref "C161") (pin "2") (pinfunction "2_2") (pintype "passive"))
      (node (ref "C163") (pin "2") (pinfunction "2_2") (pintype "passive"))
      (node (ref "IC16") (pin "4") (pinfunction "VCP_4") (pintype "power_in"))
      (node (ref "L8") (pin "1") (pinfunction "1_1") (pintype "passive"))
    )
    (net (code "105") (name "Net-(Tr3-Pri+)") (class "Default")
      (node (ref "C422") (pin "2") (pinfunction "2_2") (pintype "passive"))
      (node (ref "R65") (pin "2") (pinfunction "2_2") (pintype "passive"))
      (node (ref "Tr3") (pin "6") (pinfunction "Pri+_6") (pintype "passive"))
    )
    (net (code "106") (name "unconnected-(IC12-VBB-Pad15)") (class "Default")
      (node (ref "IC12") (pin "15") (pinfunction "VBB_15") (pintype "power_in"))
    )
    (net (code "107") (name "unconnected-(IC13A-OSC_OUT-Pad23)") (class "Default")
      (node (ref "IC13") (pin "23") (pinfunction "OSC_OUT_23") (pintype "output"))
    )
    (net (code "108") (name "unconnected-(IC16A-CLK-Pad13)") (class "Default")
      (node (ref "IC16") (pin "13") (pinfunction "CLK_13") (pintype "input+no_connect"))
    )
    (net (code "109") (name "unconnected-(IC16A-REFMON-Pad2)") (class "Default")
      (node (ref "IC16") (pin "2") (pinfunction "REFMON_2") (pintype "output"))
    )
    (net (code "110") (name "unconnected-(IC16A-~{CLK}-Pad14)") (class "Default")
      (node (ref "IC16") (pin "14") (pinfunction "~{CLK}_14") (pintype "input+no_connect"))
    )
    (net (code "111") (name "unconnected-(IC16A-~{OUT9}_(OUT9B)-Pad36)") (class "Default")
      (node (ref "IC16") (pin "36") (pinfunction "~{OUT9}_(OUT9B)_36") (pintype "output"))
    )
  )
)
